# EN715_ExpansionBoard_ver1_0.net
KiCad netlist of a schematic drawn in EAGLE
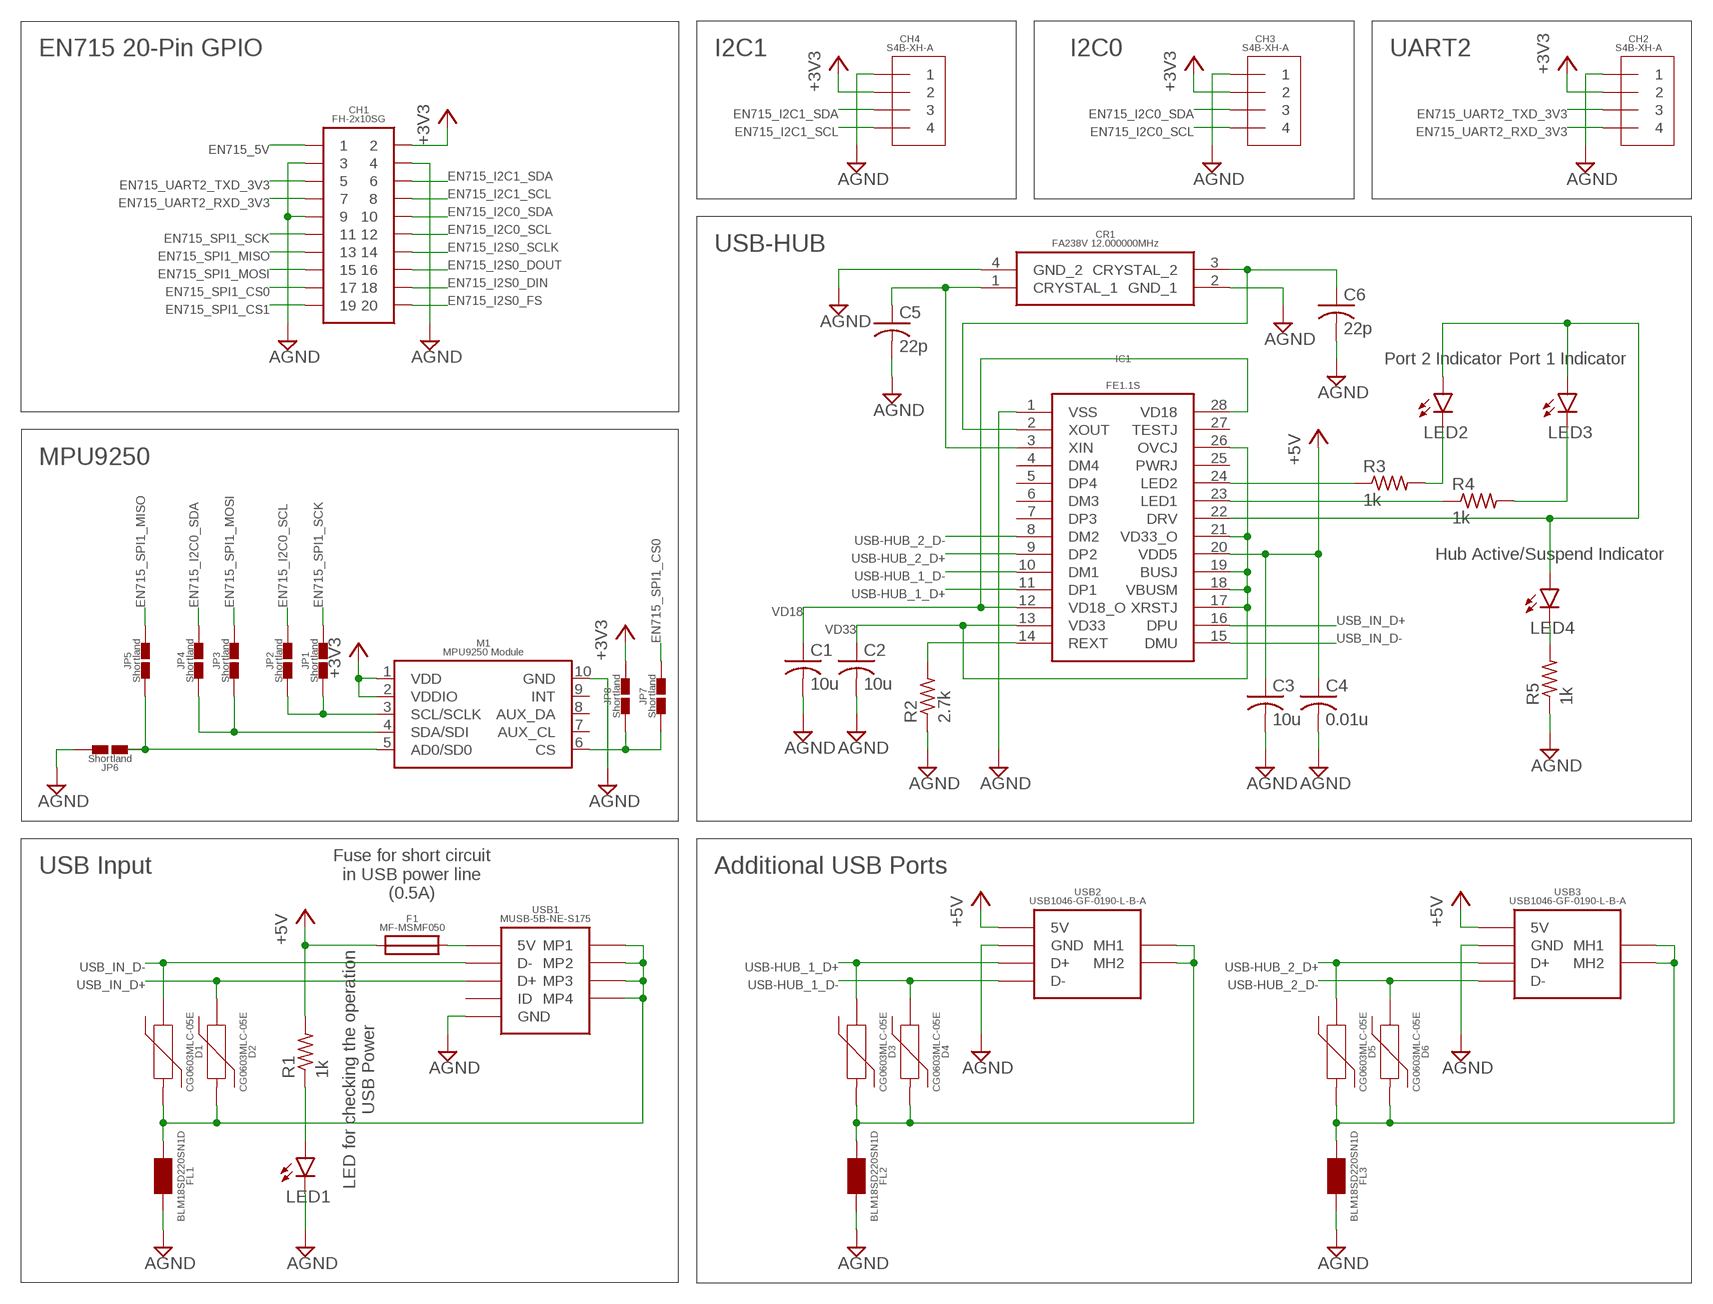
[diagram p0: schematic, sheet 1]

(export (version "E")
  (design (tool "Eeschema 10.0.6"))
  (components
    (comp (ref "C1")
      (value "10u")
      (footprint "eagle-import:C0603")
      (libsource (lib "eagle-import") (part "C-USC0603"))
    )
    (comp (ref "C2")
      (value "10u")
      (footprint "eagle-import:C0603")
      (libsource (lib "eagle-import") (part "C-USC0603"))
    )
    (comp (ref "C3")
      (value "10u")
      (footprint "eagle-import:C0603")
      (libsource (lib "eagle-import") (part "C-USC0603"))
    )
    (comp (ref "C4")
      (value "0.01u")
      (footprint "eagle-import:C0603")
      (libsource (lib "eagle-import") (part "C-USC0603"))
    )
    (comp (ref "C5")
      (value "22p")
      (footprint "eagle-import:C0603")
      (libsource (lib "eagle-import") (part "C-USC0603"))
    )
    (comp (ref "C6")
      (value "22p")
      (footprint "eagle-import:C0603")
      (libsource (lib "eagle-import") (part "C-USC0603"))
    )
    (comp (ref "CH1")
      (value "2X10")
      (footprint "eagle-import:2X10")
      (libsource (lib "eagle-import") (part "2X10"))
    )
    (comp (ref "CH2")
      (value "S4B-XH-A")
      (footprint "eagle-import:S4B-XH-A")
      (libsource (lib "eagle-import") (part "S4B-XH-A"))
    )
    (comp (ref "CH3")
      (value "S4B-XH-A")
      (footprint "eagle-import:S4B-XH-A")
      (libsource (lib "eagle-import") (part "S4B-XH-A"))
    )
    (comp (ref "CH4")
      (value "S4B-XH-A")
      (footprint "eagle-import:S4B-XH-A")
      (libsource (lib "eagle-import") (part "S4B-XH-A"))
    )
    (comp (ref "CR1")
      (value "FA238V_12.000000MHZ")
      (footprint "eagle-import:FA238V")
      (libsource (lib "eagle-import") (part "FA238V_12.000000MHZ"))
    )
    (comp (ref "D1")
      (value "CG0603MLC-05E")
      (footprint "eagle-import:CG0603MLC-05E")
      (libsource (lib "eagle-import") (part "CG0603MLC-05E"))
    )
    (comp (ref "D2")
      (value "CG0603MLC-05E")
      (footprint "eagle-import:CG0603MLC-05E")
      (libsource (lib "eagle-import") (part "CG0603MLC-05E"))
    )
    (comp (ref "D3")
      (value "CG0603MLC-05E")
      (footprint "eagle-import:CG0603MLC-05E")
      (libsource (lib "eagle-import") (part "CG0603MLC-05E"))
    )
    (comp (ref "D4")
      (value "CG0603MLC-05E")
      (footprint "eagle-import:CG0603MLC-05E")
      (libsource (lib "eagle-import") (part "CG0603MLC-05E"))
    )
    (comp (ref "D5")
      (value "CG0603MLC-05E")
      (footprint "eagle-import:CG0603MLC-05E")
      (libsource (lib "eagle-import") (part "CG0603MLC-05E"))
    )
    (comp (ref "D6")
      (value "CG0603MLC-05E")
      (footprint "eagle-import:CG0603MLC-05E")
      (libsource (lib "eagle-import") (part "CG0603MLC-05E"))
    )
    (comp (ref "F1")
      (value "MF-MSMF050")
      (footprint "eagle-import:MF-MSMF050")
      (libsource (lib "eagle-import") (part "MF-MSMF050"))
    )
    (comp (ref "FL1")
      (value "BLM18SD220SN1D")
      (footprint "eagle-import:BLM18SD220SN1D")
      (libsource (lib "eagle-import") (part "BLM18SD220SN1D"))
    )
    (comp (ref "FL2")
      (value "BLM18SD220SN1D")
      (footprint "eagle-import:BLM18SD220SN1D")
      (libsource (lib "eagle-import") (part "BLM18SD220SN1D"))
    )
    (comp (ref "FL3")
      (value "BLM18SD220SN1D")
      (footprint "eagle-import:BLM18SD220SN1D")
      (libsource (lib "eagle-import") (part "BLM18SD220SN1D"))
    )
    (comp (ref "IC1")
      (value "FE1.1S")
      (footprint "eagle-import:FE1.1S")
      (libsource (lib "eagle-import") (part "FE1.1S"))
    )
    (comp (ref "JP1")
      (value "SHORTLAND")
      (footprint "eagle-import:SHORTLAND")
      (libsource (lib "eagle-import") (part "SHORTLAND"))
    )
    (comp (ref "JP2")
      (value "SHORTLAND")
      (footprint "eagle-import:SHORTLAND")
      (libsource (lib "eagle-import") (part "SHORTLAND"))
    )
    (comp (ref "JP3")
      (value "SHORTLAND")
      (footprint "eagle-import:SHORTLAND")
      (libsource (lib "eagle-import") (part "SHORTLAND"))
    )
    (comp (ref "JP4")
      (value "SHORTLAND")
      (footprint "eagle-import:SHORTLAND")
      (libsource (lib "eagle-import") (part "SHORTLAND"))
    )
    (comp (ref "JP5")
      (value "SHORTLAND")
      (footprint "eagle-import:SHORTLAND")
      (libsource (lib "eagle-import") (part "SHORTLAND"))
    )
    (comp (ref "JP6")
      (value "SHORTLAND")
      (footprint "eagle-import:SHORTLAND")
      (libsource (lib "eagle-import") (part "SHORTLAND"))
    )
    (comp (ref "JP7")
      (value "SHORTLAND")
      (footprint "eagle-import:SHORTLAND")
      (libsource (lib "eagle-import") (part "SHORTLAND"))
    )
    (comp (ref "JP8")
      (value "SHORTLAND")
      (footprint "eagle-import:SHORTLAND")
      (libsource (lib "eagle-import") (part "SHORTLAND"))
    )
    (comp (ref "LED1")
      (value "LEDSML0603")
      (footprint "eagle-import:SML0603")
      (libsource (lib "eagle-import") (part "LEDSML0603"))
    )
    (comp (ref "LED2")
      (value "LEDSML0603")
      (footprint "eagle-import:SML0603")
      (libsource (lib "eagle-import") (part "LEDSML0603"))
    )
    (comp (ref "LED3")
      (value "LEDSML0603")
      (footprint "eagle-import:SML0603")
      (libsource (lib "eagle-import") (part "LEDSML0603"))
    )
    (comp (ref "LED4")
      (value "LEDSML0603")
      (footprint "eagle-import:SML0603")
      (libsource (lib "eagle-import") (part "LEDSML0603"))
    )
    (comp (ref "M1")
      (value "MPU9250_MODULE")
      (footprint "eagle-import:MPU9250_MODULE")
      (libsource (lib "eagle-import") (part "MPU9250_MODULE"))
    )
    (comp (ref "R1")
      (value "1k")
      (footprint "eagle-import:R0603")
      (libsource (lib "eagle-import") (part "R-US_R0603"))
    )
    (comp (ref "R2")
      (value "2.7k")
      (footprint "eagle-import:R0603")
      (libsource (lib "eagle-import") (part "R-US_R0603"))
    )
    (comp (ref "R3")
      (value "1k")
      (footprint "eagle-import:R0603")
      (libsource (lib "eagle-import") (part "R-US_R0603"))
    )
    (comp (ref "R4")
      (value "1k")
      (footprint "eagle-import:R0603")
      (libsource (lib "eagle-import") (part "R-US_R0603"))
    )
    (comp (ref "R5")
      (value "1k")
      (footprint "eagle-import:R0603")
      (libsource (lib "eagle-import") (part "R-US_R0603"))
    )
    (comp (ref "USB1")
      (value "MINI_USB_B_SMD")
      (footprint "eagle-import:MINI_USB_B_SMD")
      (libsource (lib "eagle-import") (part "MINI_USB_B_SMD"))
    )
    (comp (ref "USB2")
      (value "USB_A_X1_SMD")
      (footprint "eagle-import:USB_A_X1_SMD")
      (libsource (lib "eagle-import") (part "USB_A_X1_SMD"))
    )
    (comp (ref "USB3")
      (value "USB_A_X1_SMD")
      (footprint "eagle-import:USB_A_X1_SMD")
      (libsource (lib "eagle-import") (part "USB_A_X1_SMD"))
    )
  )
  (nets
    (net (code "1") (name "+3V3") (class "Default")
      (node (ref "CH1") (pin "2") (pinfunction "2_2") (pintype "bidirectional"))
      (node (ref "CH2") (pin "2") (pinfunction "2_2") (pintype "bidirectional"))
      (node (ref "CH3") (pin "2") (pinfunction "2_2") (pintype "bidirectional"))
      (node (ref "CH4") (pin "2") (pinfunction "2_2") (pintype "bidirectional"))
      (node (ref "JP8") (pin "2") (pinfunction "2_2") (pintype "bidirectional"))
      (node (ref "M1") (pin "1") (pinfunction "VDD_1") (pintype "bidirectional"))
      (node (ref "M1") (pin "2") (pinfunction "VDDIO_2") (pintype "bidirectional"))
    )
    (net (code "2") (name "+5V") (class "Default")
      (node (ref "C3") (pin "1") (pinfunction "1_1") (pintype "passive"))
      (node (ref "C4") (pin "1") (pinfunction "1_1") (pintype "passive"))
      (node (ref "F1") (pin "1") (pinfunction "1_1") (pintype "bidirectional"))
      (node (ref "IC1") (pin "20") (pinfunction "VDD5_20") (pintype "bidirectional"))
      (node (ref "R1") (pin "2") (pinfunction "2_2") (pintype "passive"))
      (node (ref "USB2") (pin "1") (pinfunction "5V_1") (pintype "bidirectional"))
      (node (ref "USB3") (pin "1") (pinfunction "5V_1") (pintype "bidirectional"))
    )
    (net (code "3") (name "/EN715_5V") (class "Default")
      (node (ref "CH1") (pin "1") (pinfunction "1_1") (pintype "bidirectional"))
    )
    (net (code "4") (name "/EN715_I2C0_SCL") (class "Default")
      (node (ref "CH1") (pin "12") (pinfunction "12_12") (pintype "bidirectional"))
      (node (ref "CH3") (pin "4") (pinfunction "4_4") (pintype "bidirectional"))
      (node (ref "JP2") (pin "2") (pinfunction "2_2") (pintype "bidirectional"))
    )
    (net (code "5") (name "/EN715_I2C0_SDA") (class "Default")
      (node (ref "CH1") (pin "10") (pinfunction "10_10") (pintype "bidirectional"))
      (node (ref "CH3") (pin "3") (pinfunction "3_3") (pintype "bidirectional"))
      (node (ref "JP4") (pin "2") (pinfunction "2_2") (pintype "bidirectional"))
    )
    (net (code "6") (name "/EN715_I2C1_SCL") (class "Default")
      (node (ref "CH1") (pin "8") (pinfunction "8_8") (pintype "bidirectional"))
      (node (ref "CH4") (pin "4") (pinfunction "4_4") (pintype "bidirectional"))
    )
    (net (code "7") (name "/EN715_I2C1_SDA") (class "Default")
      (node (ref "CH1") (pin "6") (pinfunction "6_6") (pintype "bidirectional"))
      (node (ref "CH4") (pin "3") (pinfunction "3_3") (pintype "bidirectional"))
    )
    (net (code "8") (name "/EN715_I2S0_DIN") (class "Default")
      (node (ref "CH1") (pin "18") (pinfunction "18_18") (pintype "bidirectional"))
    )
    (net (code "9") (name "/EN715_I2S0_DOUT") (class "Default")
      (node (ref "CH1") (pin "16") (pinfunction "16_16") (pintype "bidirectional"))
    )
    (net (code "10") (name "/EN715_I2S0_FS") (class "Default")
      (node (ref "CH1") (pin "20") (pinfunction "20_20") (pintype "bidirectional"))
    )
    (net (code "11") (name "/EN715_I2S0_SCLK") (class "Default")
      (node (ref "CH1") (pin "14") (pinfunction "14_14") (pintype "bidirectional"))
    )
    (net (code "12") (name "/EN715_SPI1_CS0") (class "Default")
      (node (ref "CH1") (pin "17") (pinfunction "17_17") (pintype "bidirectional"))
      (node (ref "JP7") (pin "2") (pinfunction "2_2") (pintype "bidirectional"))
    )
    (net (code "13") (name "/EN715_SPI1_CS1") (class "Default")
      (node (ref "CH1") (pin "19") (pinfunction "19_19") (pintype "bidirectional"))
    )
    (net (code "14") (name "/EN715_SPI1_MISO") (class "Default")
      (node (ref "CH1") (pin "13") (pinfunction "13_13") (pintype "bidirectional"))
      (node (ref "JP5") (pin "2") (pinfunction "2_2") (pintype "bidirectional"))
    )
    (net (code "15") (name "/EN715_SPI1_MOSI") (class "Default")
      (node (ref "CH1") (pin "15") (pinfunction "15_15") (pintype "bidirectional"))
      (node (ref "JP3") (pin "2") (pinfunction "2_2") (pintype "bidirectional"))
    )
    (net (code "16") (name "/EN715_SPI1_SCK") (class "Default")
      (node (ref "CH1") (pin "11") (pinfunction "11_11") (pintype "bidirectional"))
      (node (ref "JP1") (pin "2") (pinfunction "2_2") (pintype "bidirectional"))
    )
    (net (code "17") (name "/EN715_UART2_RXD_3V3") (class "Default")
      (node (ref "CH1") (pin "7") (pinfunction "7_7") (pintype "bidirectional"))
      (node (ref "CH2") (pin "4") (pinfunction "4_4") (pintype "bidirectional"))
    )
    (net (code "18") (name "/EN715_UART2_TXD_3V3") (class "Default")
      (node (ref "CH1") (pin "5") (pinfunction "5_5") (pintype "bidirectional"))
      (node (ref "CH2") (pin "3") (pinfunction "3_3") (pintype "bidirectional"))
    )
    (net (code "19") (name "/USB-HUB_1_D+") (class "Default")
      (node (ref "D3") (pin "1") (pinfunction "1_1") (pintype "bidirectional"))
      (node (ref "IC1") (pin "11") (pinfunction "DP1_11") (pintype "bidirectional"))
      (node (ref "USB2") (pin "3") (pinfunction "D+_3") (pintype "bidirectional"))
    )
    (net (code "20") (name "/USB-HUB_1_D-") (class "Default")
      (node (ref "D4") (pin "1") (pinfunction "1_1") (pintype "bidirectional"))
      (node (ref "IC1") (pin "10") (pinfunction "DM1_10") (pintype "bidirectional"))
      (node (ref "USB2") (pin "2") (pinfunction "D-_2") (pintype "bidirectional"))
    )
    (net (code "21") (name "/USB-HUB_2_D+") (class "Default")
      (node (ref "D5") (pin "1") (pinfunction "1_1") (pintype "bidirectional"))
      (node (ref "IC1") (pin "9") (pinfunction "DP2_9") (pintype "bidirectional"))
      (node (ref "USB3") (pin "3") (pinfunction "D+_3") (pintype "bidirectional"))
    )
    (net (code "22") (name "/USB-HUB_2_D-") (class "Default")
      (node (ref "D6") (pin "1") (pinfunction "1_1") (pintype "bidirectional"))
      (node (ref "IC1") (pin "8") (pinfunction "DM2_8") (pintype "bidirectional"))
      (node (ref "USB3") (pin "2") (pinfunction "D-_2") (pintype "bidirectional"))
    )
    (net (code "23") (name "/USB_IN_D+") (class "Default")
      (node (ref "D2") (pin "1") (pinfunction "1_1") (pintype "bidirectional"))
      (node (ref "IC1") (pin "16") (pinfunction "DPU_16") (pintype "bidirectional"))
      (node (ref "USB1") (pin "3") (pinfunction "D+_3") (pintype "bidirectional"))
    )
    (net (code "24") (name "/USB_IN_D-") (class "Default")
      (node (ref "D1") (pin "1") (pinfunction "1_1") (pintype "bidirectional"))
      (node (ref "IC1") (pin "15") (pinfunction "DMU_15") (pintype "bidirectional"))
      (node (ref "USB1") (pin "2") (pinfunction "D-_2") (pintype "bidirectional"))
    )
    (net (code "25") (name "/VD18") (class "Default")
      (node (ref "C1") (pin "1") (pinfunction "1_1") (pintype "passive"))
      (node (ref "IC1") (pin "12") (pinfunction "VD18_O_12") (pintype "bidirectional"))
      (node (ref "IC1") (pin "28") (pinfunction "VD18_28") (pintype "bidirectional"))
    )
    (net (code "26") (name "/VD33") (class "Default")
      (node (ref "C2") (pin "1") (pinfunction "1_1") (pintype "passive"))
      (node (ref "IC1") (pin "13") (pinfunction "VD33_13") (pintype "bidirectional"))
      (node (ref "IC1") (pin "17") (pinfunction "XRSTJ_17") (pintype "bidirectional"))
      (node (ref "IC1") (pin "18") (pinfunction "VBUSM_18") (pintype "bidirectional"))
      (node (ref "IC1") (pin "19") (pinfunction "BUSJ_19") (pintype "bidirectional"))
      (node (ref "IC1") (pin "21") (pinfunction "VD33_O_21") (pintype "bidirectional"))
      (node (ref "IC1") (pin "26") (pinfunction "OVCJ_26") (pintype "bidirectional"))
    )
    (net (code "27") (name "AGND") (class "Default")
      (node (ref "C1") (pin "2") (pinfunction "2_2") (pintype "passive"))
      (node (ref "C2") (pin "2") (pinfunction "2_2") (pintype "passive"))
      (node (ref "C3") (pin "2") (pinfunction "2_2") (pintype "passive"))
      (node (ref "C4") (pin "2") (pinfunction "2_2") (pintype "passive"))
      (node (ref "C5") (pin "2") (pinfunction "2_2") (pintype "passive"))
      (node (ref "C6") (pin "2") (pinfunction "2_2") (pintype "passive"))
      (node (ref "CH1") (pin "3") (pinfunction "3_3") (pintype "bidirectional"))
      (node (ref "CH1") (pin "4") (pinfunction "4_4") (pintype "bidirectional"))
      (node (ref "CH1") (pin "9") (pinfunction "9_9") (pintype "bidirectional"))
      (node (ref "CH2") (pin "1") (pinfunction "1_1") (pintype "bidirectional"))
      (node (ref "CH3") (pin "1") (pinfunction "1_1") (pintype "bidirectional"))
      (node (ref "CH4") (pin "1") (pinfunction "1_1") (pintype "bidirectional"))
      (node (ref "CR1") (pin "2") (pinfunction "GND_1_2") (pintype "bidirectional"))
      (node (ref "CR1") (pin "4") (pinfunction "GND_2_4") (pintype "bidirectional"))
      (node (ref "FL1") (pin "2") (pinfunction "2_2") (pintype "bidirectional"))
      (node (ref "FL2") (pin "2") (pinfunction "2_2") (pintype "bidirectional"))
      (node (ref "FL3") (pin "2") (pinfunction "2_2") (pintype "bidirectional"))
      (node (ref "IC1") (pin "1") (pinfunction "VSS_1") (pintype "bidirectional"))
      (node (ref "JP6") (pin "2") (pinfunction "2_2") (pintype "bidirectional"))
      (node (ref "LED1") (pin "C") (pinfunction "C_C") (pintype "passive"))
      (node (ref "M1") (pin "10") (pinfunction "GND_10") (pintype "bidirectional"))
      (node (ref "R2") (pin "1") (pinfunction "1_1") (pintype "passive"))
      (node (ref "R5") (pin "1") (pinfunction "1_1") (pintype "passive"))
      (node (ref "USB1") (pin "5") (pinfunction "GND_5") (pintype "bidirectional"))
      (node (ref "USB2") (pin "4") (pinfunction "GND_4") (pintype "bidirectional"))
      (node (ref "USB3") (pin "4") (pinfunction "GND_4") (pintype "bidirectional"))
    )
    (net (code "28") (name "Net-(CR1-CRYSTAL_1)") (class "Default")
      (node (ref "C5") (pin "1") (pinfunction "1_1") (pintype "passive"))
      (node (ref "CR1") (pin "1") (pinfunction "CRYSTAL_1_1") (pintype "bidirectional"))
      (node (ref "IC1") (pin "3") (pinfunction "XIN_3") (pintype "bidirectional"))
    )
    (net (code "29") (name "Net-(CR1-CRYSTAL_2)") (class "Default")
      (node (ref "C6") (pin "1") (pinfunction "1_1") (pintype "passive"))
      (node (ref "CR1") (pin "3") (pinfunction "CRYSTAL_2_3") (pintype "bidirectional"))
      (node (ref "IC1") (pin "2") (pinfunction "XOUT_2") (pintype "bidirectional"))
    )
    (net (code "30") (name "Net-(D1-Pad2)") (class "Default")
      (node (ref "D1") (pin "2") (pinfunction "2_2") (pintype "bidirectional"))
      (node (ref "D2") (pin "2") (pinfunction "2_2") (pintype "bidirectional"))
      (node (ref "FL1") (pin "1") (pinfunction "1_1") (pintype "bidirectional"))
      (node (ref "USB1") (pin "MP1") (pinfunction "MP1_MP1") (pintype "bidirectional"))
      (node (ref "USB1") (pin "MP2") (pinfunction "MP2_MP2") (pintype "bidirectional"))
      (node (ref "USB1") (pin "MP3") (pinfunction "MP3_MP3") (pintype "bidirectional"))
      (node (ref "USB1") (pin "MP4") (pinfunction "MP4_MP4") (pintype "bidirectional"))
    )
    (net (code "31") (name "Net-(D3-Pad2)") (class "Default")
      (node (ref "D3") (pin "2") (pinfunction "2_2") (pintype "bidirectional"))
      (node (ref "D4") (pin "2") (pinfunction "2_2") (pintype "bidirectional"))
      (node (ref "FL2") (pin "1") (pinfunction "1_1") (pintype "bidirectional"))
      (node (ref "USB2") (pin "MH1") (pinfunction "MH1_MH1") (pintype "bidirectional"))
      (node (ref "USB2") (pin "MH2") (pinfunction "MH2_MH2") (pintype "bidirectional"))
    )
    (net (code "32") (name "Net-(D5-Pad2)") (class "Default")
      (node (ref "D5") (pin "2") (pinfunction "2_2") (pintype "bidirectional"))
      (node (ref "D6") (pin "2") (pinfunction "2_2") (pintype "bidirectional"))
      (node (ref "FL3") (pin "1") (pinfunction "1_1") (pintype "bidirectional"))
      (node (ref "USB3") (pin "MH1") (pinfunction "MH1_MH1") (pintype "bidirectional"))
      (node (ref "USB3") (pin "MH2") (pinfunction "MH2_MH2") (pintype "bidirectional"))
    )
    (net (code "33") (name "Net-(IC1-DRV)") (class "Default")
      (node (ref "IC1") (pin "22") (pinfunction "DRV_22") (pintype "bidirectional"))
      (node (ref "LED2") (pin "A") (pinfunction "A_A") (pintype "passive"))
      (node (ref "LED3") (pin "A") (pinfunction "A_A") (pintype "passive"))
      (node (ref "LED4") (pin "A") (pinfunction "A_A") (pintype "passive"))
    )
    (net (code "34") (name "Net-(IC1-LED1)") (class "Default")
      (node (ref "IC1") (pin "23") (pinfunction "LED1_23") (pintype "bidirectional"))
      (node (ref "R4") (pin "1") (pinfunction "1_1") (pintype "passive"))
    )
    (net (code "35") (name "Net-(IC1-LED2)") (class "Default")
      (node (ref "IC1") (pin "24") (pinfunction "LED2_24") (pintype "bidirectional"))
      (node (ref "R3") (pin "1") (pinfunction "1_1") (pintype "passive"))
    )
    (net (code "36") (name "Net-(IC1-REXT)") (class "Default")
      (node (ref "IC1") (pin "14") (pinfunction "REXT_14") (pintype "bidirectional"))
      (node (ref "R2") (pin "2") (pinfunction "2_2") (pintype "passive"))
    )
    (net (code "37") (name "Net-(LED1-PadA)") (class "Default")
      (node (ref "LED1") (pin "A") (pinfunction "A_A") (pintype "passive"))
      (node (ref "R1") (pin "1") (pinfunction "1_1") (pintype "passive"))
    )
    (net (code "38") (name "Net-(LED2-PadC)") (class "Default")
      (node (ref "LED2") (pin "C") (pinfunction "C_C") (pintype "passive"))
      (node (ref "R3") (pin "2") (pinfunction "2_2") (pintype "passive"))
    )
    (net (code "39") (name "Net-(LED3-PadC)") (class "Default")
      (node (ref "LED3") (pin "C") (pinfunction "C_C") (pintype "passive"))
      (node (ref "R4") (pin "2") (pinfunction "2_2") (pintype "passive"))
    )
    (net (code "40") (name "Net-(LED4-PadC)") (class "Default")
      (node (ref "LED4") (pin "C") (pinfunction "C_C") (pintype "passive"))
      (node (ref "R5") (pin "2") (pinfunction "2_2") (pintype "passive"))
    )
    (net (code "41") (name "Net-(M1-AD0{slash}SD0)") (class "Default")
      (node (ref "JP5") (pin "1") (pinfunction "1_1") (pintype "bidirectional"))
      (node (ref "JP6") (pin "1") (pinfunction "1_1") (pintype "bidirectional"))
      (node (ref "M1") (pin "5") (pinfunction "AD0/SD0_5") (pintype "bidirectional"))
    )
    (net (code "42") (name "Net-(M1-CS)") (class "Default")
      (node (ref "JP7") (pin "1") (pinfunction "1_1") (pintype "bidirectional"))
      (node (ref "JP8") (pin "1") (pinfunction "1_1") (pintype "bidirectional"))
      (node (ref "M1") (pin "6") (pinfunction "CS_6") (pintype "bidirectional"))
    )
    (net (code "43") (name "Net-(M1-SCL{slash}SCLK)") (class "Default")
      (node (ref "JP1") (pin "1") (pinfunction "1_1") (pintype "bidirectional"))
      (node (ref "JP2") (pin "1") (pinfunction "1_1") (pintype "bidirectional"))
      (node (ref "M1") (pin "3") (pinfunction "SCL/SCLK_3") (pintype "bidirectional"))
    )
    (net (code "44") (name "Net-(M1-SDA{slash}SDI)") (class "Default")
      (node (ref "JP3") (pin "1") (pinfunction "1_1") (pintype "bidirectional"))
      (node (ref "JP4") (pin "1") (pinfunction "1_1") (pintype "bidirectional"))
      (node (ref "M1") (pin "4") (pinfunction "SDA/SDI_4") (pintype "bidirectional"))
    )
    (net (code "45") (name "Net-(USB1-5V)") (class "Default")
      (node (ref "F1") (pin "2") (pinfunction "2_2") (pintype "bidirectional"))
      (node (ref "USB1") (pin "1") (pinfunction "5V_1") (pintype "bidirectional"))
    )
    (net (code "46") (name "unconnected-(IC1-DM3-Pad6)") (class "Default")
      (node (ref "IC1") (pin "6") (pinfunction "DM3_6") (pintype "bidirectional"))
    )
    (net (code "47") (name "unconnected-(IC1-DM4-Pad4)") (class "Default")
      (node (ref "IC1") (pin "4") (pinfunction "DM4_4") (pintype "bidirectional"))
    )
    (net (code "48") (name "unconnected-(IC1-DP3-Pad7)") (class "Default")
      (node (ref "IC1") (pin "7") (pinfunction "DP3_7") (pintype "bidirectional"))
    )
    (net (code "49") (name "unconnected-(IC1-DP4-Pad5)") (class "Default")
      (node (ref "IC1") (pin "5") (pinfunction "DP4_5") (pintype "bidirectional"))
    )
    (net (code "50") (name "unconnected-(IC1-PWRJ-Pad25)") (class "Default")
      (node (ref "IC1") (pin "25") (pinfunction "PWRJ_25") (pintype "bidirectional"))
    )
    (net (code "51") (name "unconnected-(IC1-TESTJ-Pad27)") (class "Default")
      (node (ref "IC1") (pin "27") (pinfunction "TESTJ_27") (pintype "bidirectional"))
    )
    (net (code "52") (name "unconnected-(M1-AUX_CL-Pad7)") (class "Default")
      (node (ref "M1") (pin "7") (pinfunction "AUX_CL_7") (pintype "bidirectional"))
    )
    (net (code "53") (name "unconnected-(M1-AUX_DA-Pad8)") (class "Default")
      (node (ref "M1") (pin "8") (pinfunction "AUX_DA_8") (pintype "bidirectional"))
    )
    (net (code "54") (name "unconnected-(M1-INT-Pad9)") (class "Default")
      (node (ref "M1") (pin "9") (pinfunction "INT_9") (pintype "bidirectional"))
    )
    (net (code "55") (name "unconnected-(USB1-ID-Pad4)") (class "Default")
      (node (ref "USB1") (pin "4") (pinfunction "ID_4") (pintype "bidirectional"))
    )
  )
)
